# Sheet1.net
KiCad netlist of a schematic drawn in Altium Designer
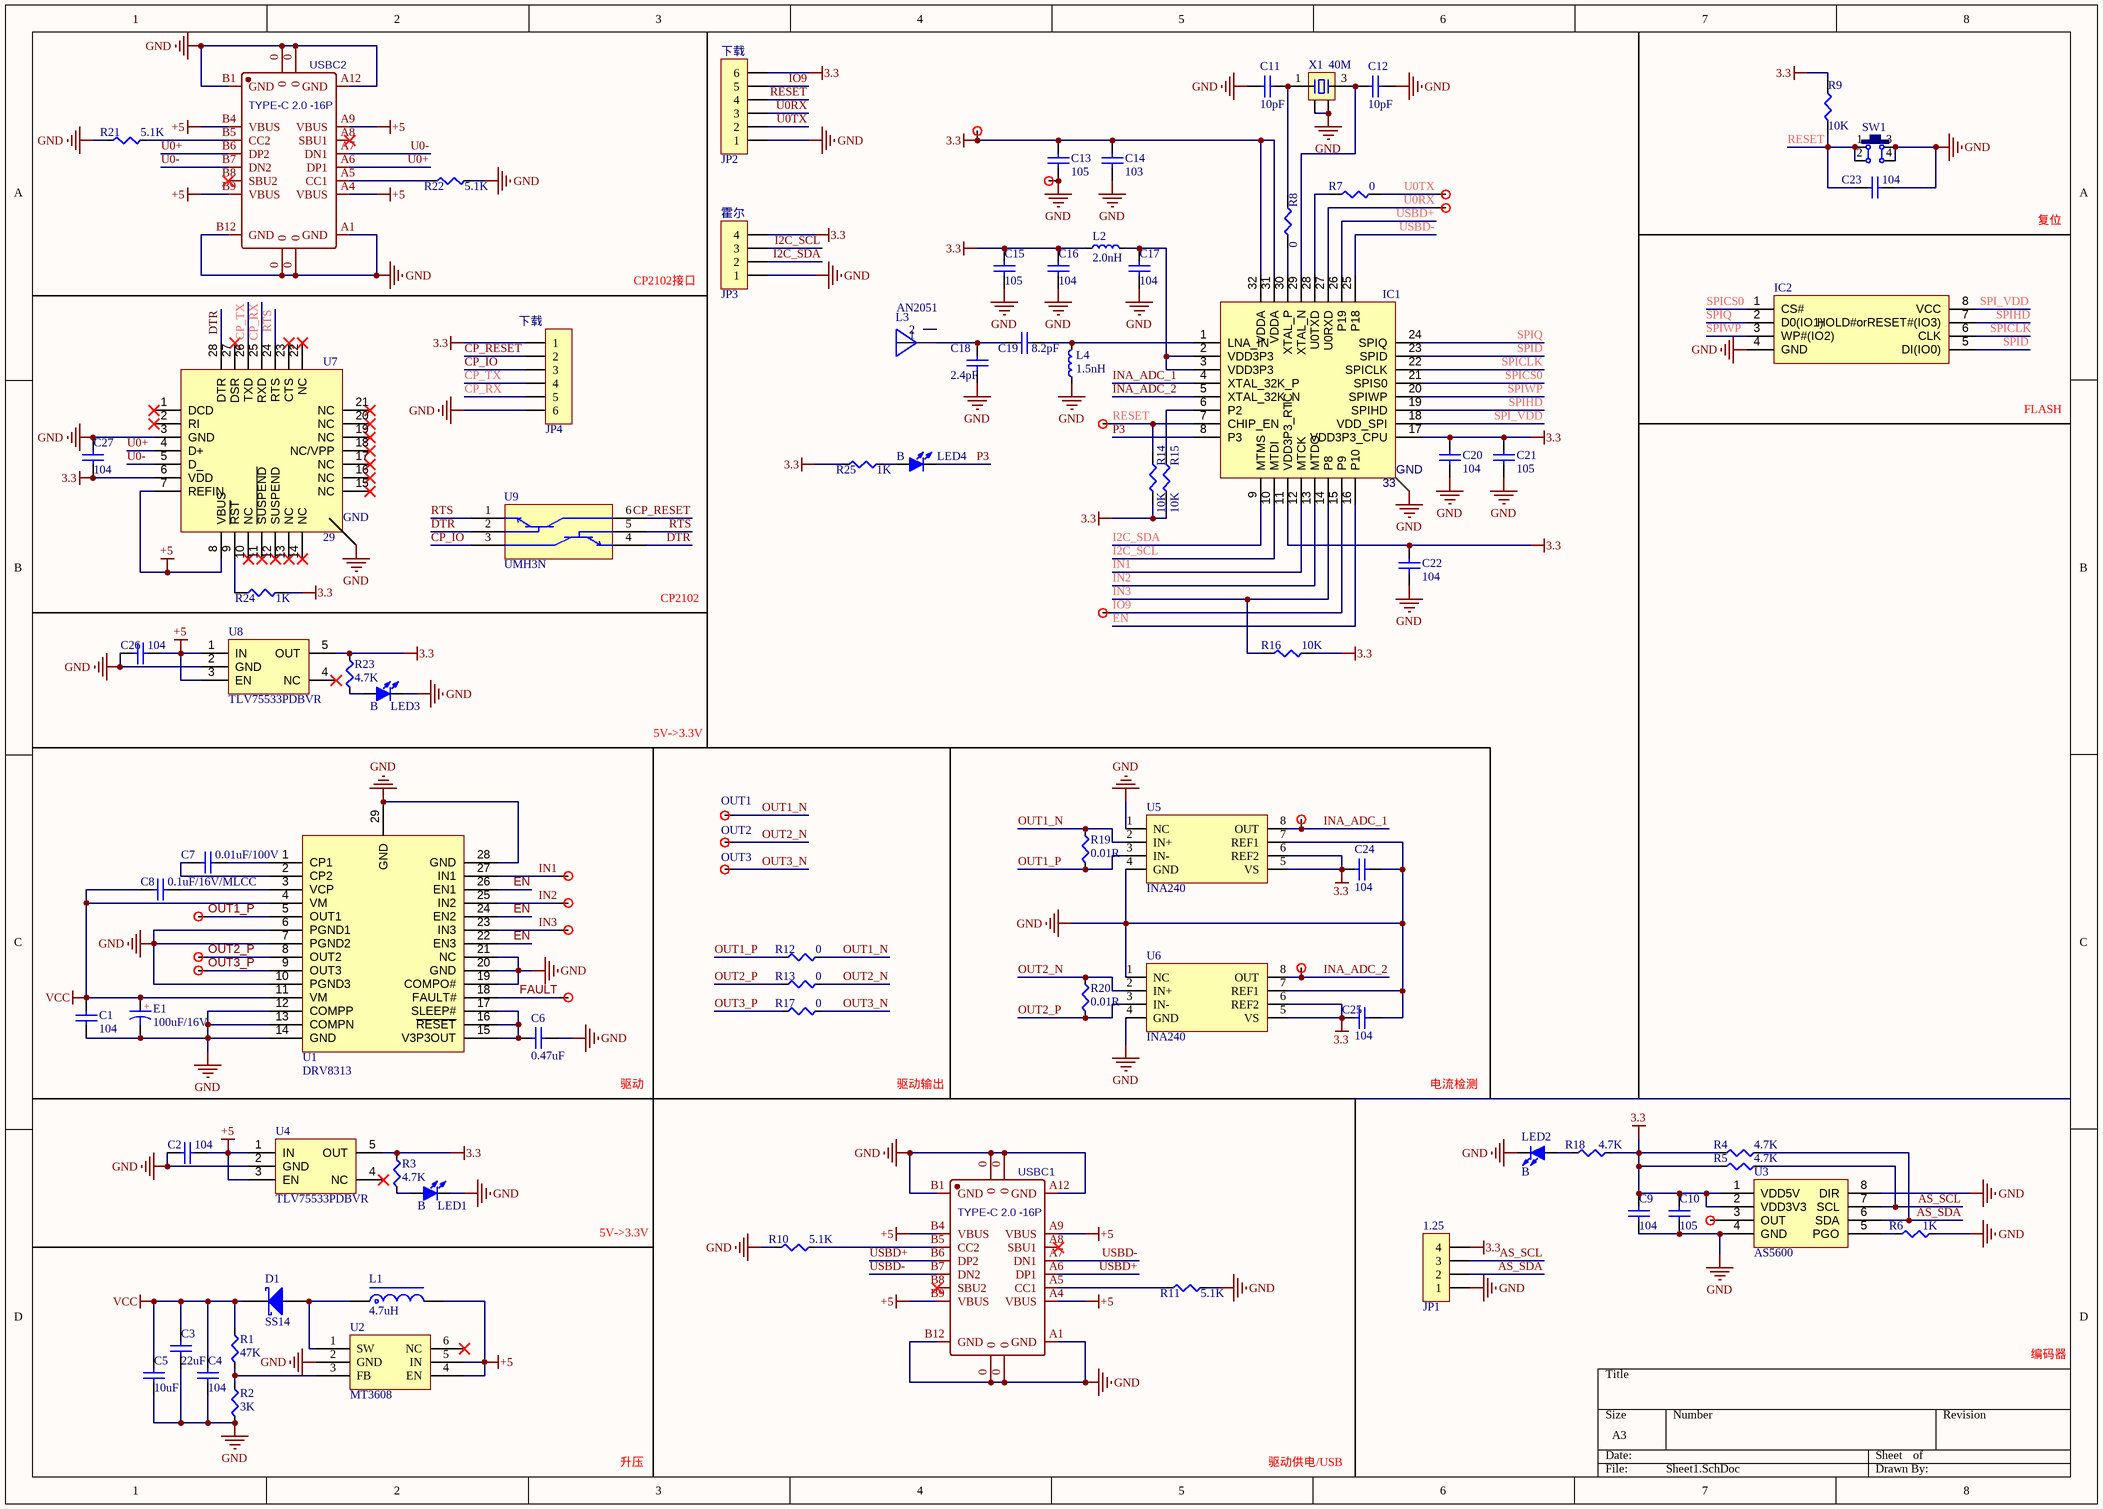
[diagram p0: Sheet1.SchDoc]

(export (version "E")
  (design (tool "Eeschema 10.0.6"))
  (components
    (comp (ref "C1")
      (value "104")
      (footprint "C 0603_L")
      (description "贴片电容")
      (libsource (lib "0.1 - 电阻-电容-电感") (part "C"))
    )
    (comp (ref "C2")
      (value "104")
      (footprint "C 0603_L")
      (description "贴片电容")
      (libsource (lib "0.1 - 电阻-电容-电感") (part "C"))
    )
    (comp (ref "C3")
      (value "22uF")
      (footprint "C 1206_L")
      (description "贴片电容")
      (libsource (lib "0.1 - 电阻-电容-电感") (part "C"))
    )
    (comp (ref "C4")
      (value "104")
      (footprint "C 0603_L")
      (description "贴片电容")
      (libsource (lib "0.1 - 电阻-电容-电感") (part "C"))
    )
    (comp (ref "C5")
      (value "10uF")
      (footprint "C 0603_L")
      (description "贴片电容")
      (libsource (lib "0.1 - 电阻-电容-电感") (part "C"))
    )
    (comp (ref "C6")
      (value "0.47uF")
      (footprint "C 0603_L")
      (description "贴片电容")
      (libsource (lib "0.1 - 电阻-电容-电感") (part "C"))
    )
    (comp (ref "C7")
      (value "0.01uF/100V")
      (footprint "C 0603_L")
      (description "贴片电容")
      (libsource (lib "0.1 - 电阻-电容-电感") (part "C"))
    )
    (comp (ref "C8")
      (value "0.1uF/16V/MLCC")
      (footprint "C 0603_L")
      (description "贴片电容")
      (libsource (lib "0.1 - 电阻-电容-电感") (part "C"))
    )
    (comp (ref "C9")
      (value "104")
      (footprint "C 0603_L")
      (description "贴片电容")
      (libsource (lib "0.1 - 电阻-电容-电感") (part "C"))
    )
    (comp (ref "C10")
      (value "105")
      (footprint "C 0603_L")
      (description "贴片电容")
      (libsource (lib "0.1 - 电阻-电容-电感") (part "C"))
    )
    (comp (ref "C11")
      (value "10pF")
      (footprint "C 0603_L")
      (description "贴片电容")
      (libsource (lib "0.1 - 电阻-电容-电感") (part "C"))
    )
    (comp (ref "C12")
      (value "10pF")
      (footprint "C 0603_L")
      (description "贴片电容")
      (libsource (lib "0.1 - 电阻-电容-电感") (part "C"))
    )
    (comp (ref "C13")
      (value "105")
      (footprint "C 0603_L")
      (description "贴片电容")
      (libsource (lib "0.1 - 电阻-电容-电感") (part "C"))
    )
    (comp (ref "C14")
      (value "103")
      (footprint "C 0603_L")
      (description "贴片电容")
      (libsource (lib "0.1 - 电阻-电容-电感") (part "C"))
    )
    (comp (ref "C15")
      (value "105")
      (footprint "C 0603_L")
      (description "贴片电容")
      (libsource (lib "0.1 - 电阻-电容-电感") (part "C"))
    )
    (comp (ref "C16")
      (value "104")
      (footprint "C 0603_L")
      (description "贴片电容")
      (libsource (lib "0.1 - 电阻-电容-电感") (part "C"))
    )
    (comp (ref "C17")
      (value "104")
      (footprint "C 0603_L")
      (description "贴片电容")
      (libsource (lib "0.1 - 电阻-电容-电感") (part "C"))
    )
    (comp (ref "C18")
      (value "2.4pF")
      (footprint "C 0603_L")
      (description "贴片电容")
      (libsource (lib "0.1 - 电阻-电容-电感") (part "C"))
    )
    (comp (ref "C19")
      (value "8.2pF")
      (footprint "C 0603_L")
      (description "贴片电容")
      (libsource (lib "0.1 - 电阻-电容-电感") (part "C"))
    )
    (comp (ref "C20")
      (value "104")
      (footprint "C 0603_L")
      (description "贴片电容")
      (libsource (lib "0.1 - 电阻-电容-电感") (part "C"))
    )
    (comp (ref "C21")
      (value "105")
      (footprint "C 0603_L")
      (description "贴片电容")
      (libsource (lib "0.1 - 电阻-电容-电感") (part "C"))
    )
    (comp (ref "C22")
      (value "104")
      (footprint "C 0603_L")
      (description "贴片电容")
      (libsource (lib "0.1 - 电阻-电容-电感") (part "C"))
    )
    (comp (ref "C23")
      (value "104")
      (footprint "C 0603_L")
      (description "贴片电容")
      (libsource (lib "0.1 - 电阻-电容-电感") (part "C"))
    )
    (comp (ref "C24")
      (value "104")
      (footprint "C 0603_L")
      (description "贴片电容")
      (libsource (lib "0.1 - 电阻-电容-电感") (part "C"))
    )
    (comp (ref "C25")
      (value "104")
      (footprint "C 0603_L")
      (description "贴片电容")
      (libsource (lib "0.1 - 电阻-电容-电感") (part "C"))
    )
    (comp (ref "C26")
      (value "104")
      (footprint "C 0603_L")
      (description "贴片电容")
      (libsource (lib "0.1 - 电阻-电容-电感") (part "C"))
    )
    (comp (ref "C27")
      (value "104")
      (footprint "C 0603_L")
      (description "贴片电容")
      (libsource (lib "0.1 - 电阻-电容-电感") (part "C"))
    )
    (comp (ref "D1")
      (value "SS14")
      (footprint "SMA")
      (description "肖特基二极管")
      (libsource (lib "0.2 - 二极管-整流桥") (part "SS14"))
    )
    (comp (ref "E1")
      (value "100uF/16V")
      (footprint "CM D(6.3*5.4)")
      (description "贴片电解电容")
      (libsource (lib "0.1 - 电阻-电容-电感") (part "CE_SMD"))
    )
    (comp (ref "HP1")
      (value "HP")
      (footprint "HP1x0.5")
      (description "引脚测试点")
      (libsource (lib "6.6 - 焊盘") (part "HP"))
    )
    (comp (ref "HP2")
      (value "HP")
      (footprint "HP1x0.5")
      (description "引脚测试点")
      (libsource (lib "6.6 - 焊盘") (part "HP"))
    )
    (comp (ref "HP3")
      (value "HP")
      (footprint "HP1x0.5")
      (description "引脚测试点")
      (libsource (lib "6.6 - 焊盘") (part "HP"))
    )
    (comp (ref "HP4")
      (value "HP")
      (footprint "HP1x0.5")
      (description "引脚测试点")
      (libsource (lib "6.6 - 焊盘") (part "HP"))
    )
    (comp (ref "HP5")
      (value "HP")
      (footprint "HP1x0.5")
      (description "引脚测试点")
      (libsource (lib "6.6 - 焊盘") (part "HP"))
    )
    (comp (ref "HP6")
      (value "HP")
      (footprint "HP1x0.5")
      (description "引脚测试点")
      (libsource (lib "6.6 - 焊盘") (part "HP"))
    )
    (comp (ref "HP7")
      (value "HP")
      (footprint "HP1x0.5")
      (description "引脚测试点")
      (libsource (lib "6.6 - 焊盘") (part "HP"))
    )
    (comp (ref "HP8")
      (value "HP")
      (footprint "HP1x0.5")
      (description "引脚测试点")
      (libsource (lib "6.6 - 焊盘") (part "HP"))
    )
    (comp (ref "HP9")
      (value "OUT1")
      (footprint "HP1x0.5")
      (description "引脚测试点")
      (libsource (lib "6.6 - 焊盘") (part "HP"))
    )
    (comp (ref "HP10")
      (value "OUT2")
      (footprint "HP1x0.5")
      (description "引脚测试点")
      (libsource (lib "6.6 - 焊盘") (part "HP"))
    )
    (comp (ref "HP11")
      (value "OUT3")
      (footprint "HP1x0.5")
      (description "引脚测试点")
      (libsource (lib "6.6 - 焊盘") (part "HP"))
    )
    (comp (ref "HP12")
      (value "HP")
      (footprint "HP1x0.5")
      (description "引脚测试点")
      (libsource (lib "6.6 - 焊盘") (part "HP"))
    )
    (comp (ref "HP13")
      (value "HP")
      (footprint "HP1x0.5")
      (description "引脚测试点")
      (libsource (lib "6.6 - 焊盘") (part "HP"))
    )
    (comp (ref "HP14")
      (value "HP")
      (footprint "HP1x0.5")
      (description "引脚测试点")
      (libsource (lib "6.6 - 焊盘") (part "HP"))
    )
    (comp (ref "HP15")
      (value "HP")
      (footprint "HP1x0.5")
      (description "引脚测试点")
      (libsource (lib "6.6 - 焊盘") (part "HP"))
    )
    (comp (ref "HP16")
      (value "HP")
      (footprint "HP1x0.5")
      (description "引脚测试点")
      (libsource (lib "6.6 - 焊盘") (part "HP"))
    )
    (comp (ref "HP17")
      (value "HP")
      (footprint "HP1x0.5")
      (description "引脚测试点")
      (libsource (lib "6.6 - 焊盘") (part "HP"))
    )
    (comp (ref "HP18")
      (value "HP")
      (footprint "HP1x0.5")
      (description "引脚测试点")
      (libsource (lib "6.6 - 焊盘") (part "HP"))
    )
    (comp (ref "HP19")
      (value "HP")
      (footprint "HP1x0.5")
      (description "引脚测试点")
      (libsource (lib "6.6 - 焊盘") (part "HP"))
    )
    (comp (ref "IC1")
      (value "ESP32-C3")
      (footprint "ESP32-C3")
      (description "ESP32-C3 QFN-32(5x5)")
      (libsource (lib "ESP32") (part "ESP32-C3"))
    )
    (comp (ref "IC2")
      (value "W25Q64")
      (footprint "SOIC-8W")
      (libsource (lib "1.2 - 存储器-传感元件") (part "W25Q64"))
    )
    (comp (ref "JP1")
      (value "HDR-1X4")
      (footprint "MX 1.25-WI-4P")
      (description "4P接插件")
      (libsource (lib "5.0 - 接插件-脚距1.25") (part "Header 4"))
    )
    (comp (ref "JP2")
      (value "HDR-1X6")
      (footprint "MX 1.25-WI-6P")
      (description "6P接插件")
      (libsource (lib "5.0 - 接插件-脚距1.25") (part "Header 6"))
    )
    (comp (ref "JP3")
      (value "HDR-1X4")
      (footprint "MX 1.25-WI-4P")
      (description "4P接插件")
      (libsource (lib "5.0 - 接插件-脚距1.25") (part "Header 4"))
    )
    (comp (ref "JP4")
      (value "HDR-1X6")
      (footprint "MX 1.25-WI-6P")
      (description "6P接插件")
      (libsource (lib "") (part "Header 6_1"))
    )
    (comp (ref "L1")
      (value "4.7uH")
      (footprint "NR4020")
      (description "NR磁胶电感")
      (libsource (lib "0.1 - 电阻-电容-电感") (part "L-NR"))
    )
    (comp (ref "L2")
      (value "2.0nH")
      (footprint "L 0805")
      (description "小功率贴片电感")
      (libsource (lib "0.1 - 电阻-电容-电感") (part "L"))
    )
    (comp (ref "L3")
      (value "AN2051")
      (footprint "AN2051-245 2.4G")
      (description "AN2051-245 2.4G蓝牙wifi 贴片 2051")
      (libsource (lib "1.8 - WiFi天线-SMA射频座") (part "AN2051"))
    )
    (comp (ref "L4")
      (value "1.5nH")
      (footprint "L 0805")
      (description "小功率贴片电感")
      (libsource (lib "0.1 - 电阻-电容-电感") (part "L"))
    )
    (comp (ref "LED1")
      (value "B")
      (footprint "LED 0603B")
      (description "贴片LED")
      (libsource (lib "0.3 - LED发光二极管") (part "B"))
    )
    (comp (ref "LED2")
      (value "B")
      (footprint "LED 0603B")
      (description "贴片LED")
      (libsource (lib "0.3 - LED发光二极管") (part "B"))
    )
    (comp (ref "LED3")
      (value "B")
      (footprint "LED 0603B")
      (description "贴片LED")
      (libsource (lib "0.3 - LED发光二极管") (part "B"))
    )
    (comp (ref "LED4")
      (value "B")
      (footprint "LED 0603B")
      (description "贴片LED")
      (libsource (lib "0.3 - LED发光二极管") (part "B"))
    )
    (comp (ref "R1")
      (value "47K")
      (footprint "R 0603_L")
      (description "贴片电阻")
      (libsource (lib "0.1 - 电阻-电容-电感") (part "R"))
    )
    (comp (ref "R2")
      (value "3K")
      (footprint "R 0603_L")
      (description "贴片电阻")
      (libsource (lib "0.1 - 电阻-电容-电感") (part "R"))
    )
    (comp (ref "R3")
      (value "4.7K")
      (footprint "R 0603_L")
      (description "贴片电阻")
      (libsource (lib "0.1 - 电阻-电容-电感") (part "R"))
    )
    (comp (ref "R4")
      (value "4.7K")
      (footprint "R 0603_L")
      (description "贴片电阻")
      (libsource (lib "0.1 - 电阻-电容-电感") (part "R"))
    )
    (comp (ref "R5")
      (value "4.7K")
      (footprint "R 0603_L")
      (description "贴片电阻")
      (libsource (lib "0.1 - 电阻-电容-电感") (part "R"))
    )
    (comp (ref "R6")
      (value "1K")
      (footprint "R 0603_L")
      (description "贴片电阻")
      (libsource (lib "0.1 - 电阻-电容-电感") (part "R"))
    )
    (comp (ref "R7")
      (value "0")
      (footprint "R 0603_L")
      (description "贴片电阻")
      (libsource (lib "") (part "R_1"))
    )
    (comp (ref "R8")
      (value "0")
      (footprint "R 0603_L")
      (description "贴片电阻")
      (libsource (lib "") (part "R_1"))
    )
    (comp (ref "R9")
      (value "10K")
      (footprint "R 0603_L")
      (description "贴片电阻")
      (libsource (lib "") (part "R_1"))
    )
    (comp (ref "R10")
      (value "5.1K")
      (footprint "R 0603_L")
      (description "贴片电阻")
      (libsource (lib "0.1 - 电阻-电容-电感") (part "R"))
    )
    (comp (ref "R11")
      (value "5.1K")
      (footprint "R 0603_L")
      (description "贴片电阻")
      (libsource (lib "0.1 - 电阻-电容-电感") (part "R"))
    )
    (comp (ref "R12")
      (value "0")
      (footprint "R 0603_L")
      (description "贴片电阻")
      (libsource (lib "0.1 - 电阻-电容-电感") (part "R"))
    )
    (comp (ref "R13")
      (value "0")
      (footprint "R 0603_L")
      (description "贴片电阻")
      (libsource (lib "0.1 - 电阻-电容-电感") (part "R"))
    )
    (comp (ref "R14")
      (value "10K")
      (footprint "R 0603_L")
      (description "贴片电阻")
      (libsource (lib "") (part "R_1"))
    )
    (comp (ref "R15")
      (value "10K")
      (footprint "R 0603_L")
      (description "贴片电阻")
      (libsource (lib "") (part "R_1"))
    )
    (comp (ref "R16")
      (value "10K")
      (footprint "R 0603_L")
      (description "贴片电阻")
      (libsource (lib "") (part "R_1"))
    )
    (comp (ref "R17")
      (value "0")
      (footprint "R 0603_L")
      (description "贴片电阻")
      (libsource (lib "0.1 - 电阻-电容-电感") (part "R"))
    )
    (comp (ref "R18")
      (value "4.7K")
      (footprint "R 0603_L")
      (description "贴片电阻")
      (libsource (lib "0.1 - 电阻-电容-电感") (part "R"))
    )
    (comp (ref "R19")
      (value "0.01R")
      (footprint "R 1206_L")
      (description "贴片电阻")
      (libsource (lib "0.1 - 电阻-电容-电感") (part "R"))
    )
    (comp (ref "R20")
      (value "0.01R")
      (footprint "R 1210_L")
      (description "贴片电阻")
      (libsource (lib "0.1 - 电阻-电容-电感") (part "R"))
    )
    (comp (ref "R21")
      (value "5.1K")
      (footprint "R 0603_L")
      (description "贴片电阻")
      (libsource (lib "0.1 - 电阻-电容-电感") (part "R"))
    )
    (comp (ref "R22")
      (value "5.1K")
      (footprint "R 0603_L")
      (description "贴片电阻")
      (libsource (lib "0.1 - 电阻-电容-电感") (part "R"))
    )
    (comp (ref "R23")
      (value "4.7K")
      (footprint "R 0603_L")
      (description "贴片电阻")
      (libsource (lib "0.1 - 电阻-电容-电感") (part "R"))
    )
    (comp (ref "R24")
      (value "1K")
      (footprint "R 0603_L")
      (description "贴片电阻")
      (libsource (lib "") (part "R_1"))
    )
    (comp (ref "R25")
      (value "1K")
      (footprint "R 0603_L")
      (description "贴片电阻")
      (libsource (lib "0.1 - 电阻-电容-电感") (part "R"))
    )
    (comp (ref "SW1")
      (value "3.2x4.2x5")
      (footprint "TSW SMD 3.2*4.2*2.5")
      (description "贴片4.2*3.2轻触开关")
      (libsource (lib "0.7 - 常用按键-开关-蜂鸣器-电池") (part "TSW SMD-3.2x4.2"))
    )
    (comp (ref "U1")
      (value "DRV8313")
      (footprint "HTSSOP-28-EP-4.5mm")
      (description "DRV8313 无刷直流BLDC 8V~60V三路半H桥驱动器IC")
      (libsource (lib "1.0 - 常见芯片") (part "DRV8313"))
    )
    (comp (ref "U2")
      (value "MT3608")
      (footprint "SOT23-6L")
      (description "DCDC 升压1.2MHZ 2A\r\n97%")
      (libsource (lib "1.1 - 电源类芯片") (part "MT3608"))
    )
    (comp (ref "U3")
      (value "AS5600")
      (footprint "SOIC-8")
      (description "AS5600 12bit磁角度位置传感器")
      (libsource (lib "1.0 - 常见芯片") (part "AS5600"))
    )
    (comp (ref "U4")
      (value "TLV75533PDBVR")
      (footprint "SOT23-5L")
      (description "Vout:3.3V;Vin:1.45~5.5V,500ma;低压降")
      (libsource (lib "1.1 - 电源类芯片") (part "TLV75533PDBVR"))
    )
    (comp (ref "U5")
      (value "INA240")
      (footprint "TSSOP8_N")
      (description "具有增强的 PWM 抑制能力的 -4V 至 80V、双向、超精密电流感应放大器")
      (libsource (lib "1.1 - 电源类芯片") (part "INA240"))
    )
    (comp (ref "U6")
      (value "INA240")
      (footprint "TSSOP8_N")
      (description "具有增强的 PWM 抑制能力的 -4V 至 80V、双向、超精密电流感应放大器")
      (libsource (lib "1.1 - 电源类芯片") (part "INA240"))
    )
    (comp (ref "U7")
      (value "CP2102")
      (footprint "QFN28 5x5_M")
      (description "USB转TTL")
      (libsource (lib "1.0 - 常见芯片") (part "CP2102"))
    )
    (comp (ref "U8")
      (value "TLV75533PDBVR")
      (footprint "SOT23-5L")
      (description "Vout:3.3V;Vin:1.45~5.5V,500ma;低压降")
      (libsource (lib "1.1 - 电源类芯片") (part "TLV75533PDBVR"))
    )
    (comp (ref "U9")
      (value "UMH3N")
      (footprint "SOT-363")
      (description "2NPN预偏式(双)")
      (libsource (lib "0.4 - 三极管-场效应管-可控硅") (part "UMH3N"))
    )
    (comp (ref "USBC1")
      (value "TYPE-C 2.0 -16P")
      (footprint "USB-C-SMD_TYPE-C-USB-5")
      (description "USB2.0 Type-C 母座 16Pin")
      (libsource (lib "0.8 - 以太网-音频-USB插座") (part "USB2.0 Type-C 16Pin母座"))
    )
    (comp (ref "USBC2")
      (value "TYPE-C 2.0 -16P")
      (footprint "USB-C-SMD_TYPE-C-USB-5")
      (description "USB2.0 Type-C 母座 16Pin")
      (libsource (lib "0.8 - 以太网-音频-USB插座") (part "USB2.0 Type-C 16Pin母座"))
    )
    (comp (ref "X1")
      (value "40M")
      (footprint "OSC 3225-4P")
      (description "4脚无源晶振")
      (libsource (lib "0.5 - 保险丝-晶振-光耦") (part "XTAL-4P"))
    )
  )
  (nets
    (net (code "1") (name "+5") (class "Default")
      (node (ref "C2") (pin "2") (pinfunction "2_2") (pintype "passive"))
      (node (ref "C26") (pin "2") (pinfunction "2_2") (pintype "passive"))
      (node (ref "L1") (pin "2") (pinfunction "2_2") (pintype "passive"))
      (node (ref "U2") (pin "4") (pinfunction "EN_4") (pintype "passive"))
      (node (ref "U2") (pin "5") (pinfunction "IN_5") (pintype "passive"))
      (node (ref "U4") (pin "1") (pinfunction "IN_1") (pintype "passive"))
      (node (ref "U4") (pin "3") (pinfunction "EN_3") (pintype "passive"))
      (node (ref "U7") (pin "7") (pinfunction "REFIN_7") (pintype "passive"))
      (node (ref "U7") (pin "8") (pinfunction "VBUS_8") (pintype "passive"))
      (node (ref "U8") (pin "1") (pinfunction "IN_1") (pintype "passive"))
      (node (ref "U8") (pin "3") (pinfunction "EN_3") (pintype "passive"))
      (node (ref "USBC1") (pin "A4") (pinfunction "VBUS_A4") (pintype "passive"))
      (node (ref "USBC1") (pin "A9") (pinfunction "VBUS_A9") (pintype "passive"))
      (node (ref "USBC1") (pin "B4") (pinfunction "VBUS_B4") (pintype "passive"))
      (node (ref "USBC1") (pin "B9") (pinfunction "VBUS_B9") (pintype "passive"))
      (node (ref "USBC2") (pin "A4") (pinfunction "VBUS_A4") (pintype "passive"))
      (node (ref "USBC2") (pin "A9") (pinfunction "VBUS_A9") (pintype "passive"))
      (node (ref "USBC2") (pin "B4") (pinfunction "VBUS_B4") (pintype "passive"))
      (node (ref "USBC2") (pin "B9") (pinfunction "VBUS_B9") (pintype "passive"))
    )
    (net (code "2") (name "/AS_SCL") (class "Default")
      (node (ref "JP1") (pin "3") (pinfunction "3_3") (pintype "passive"))
      (node (ref "R5") (pin "2") (pinfunction "2_2") (pintype "passive"))
      (node (ref "U3") (pin "7") (pinfunction "SCL_7") (pintype "passive"))
    )
    (net (code "3") (name "/AS_SDA") (class "Default")
      (node (ref "JP1") (pin "2") (pinfunction "2_2") (pintype "passive"))
      (node (ref "R4") (pin "2") (pinfunction "2_2") (pintype "passive"))
      (node (ref "U3") (pin "6") (pinfunction "SDA_6") (pintype "passive"))
    )
    (net (code "4") (name "/CP_IO") (class "Default")
      (node (ref "JP4") (pin "3") (pinfunction "3_3") (pintype "passive"))
      (node (ref "U9") (pin "3") (pinfunction "C2_3") (pintype "passive"))
    )
    (net (code "5") (name "/CP_RESET") (class "Default")
      (node (ref "JP4") (pin "2") (pinfunction "2_2") (pintype "passive"))
      (node (ref "U9") (pin "6") (pinfunction "C1_6") (pintype "passive"))
    )
    (net (code "6") (name "/CP_RX") (class "Default")
      (node (ref "JP4") (pin "5") (pinfunction "5_5") (pintype "passive"))
      (node (ref "U7") (pin "25") (pinfunction "RXD_25") (pintype "passive"))
    )
    (net (code "7") (name "/CP_TX") (class "Default")
      (node (ref "JP4") (pin "4") (pinfunction "4_4") (pintype "passive"))
      (node (ref "U7") (pin "26") (pinfunction "TXD_26") (pintype "passive"))
    )
    (net (code "8") (name "/DTR") (class "Default")
      (node (ref "U7") (pin "28") (pinfunction "DTR_28") (pintype "passive"))
      (node (ref "U9") (pin "2") (pinfunction "B2_2") (pintype "passive"))
      (node (ref "U9") (pin "4") (pinfunction "E2_4") (pintype "passive"))
    )
    (net (code "9") (name "/EN") (class "Default")
      (node (ref "IC1") (pin "16") (pinfunction "P10_16") (pintype "power_in"))
      (node (ref "U1") (pin "22") (pinfunction "EN3_22") (pintype "passive"))
      (node (ref "U1") (pin "24") (pinfunction "EN2_24") (pintype "passive"))
      (node (ref "U1") (pin "26") (pinfunction "EN1_26") (pintype "passive"))
    )
    (net (code "10") (name "/FAULT") (class "Default")
      (node (ref "HP7") (pin "1") (pinfunction "1_1") (pintype "passive"))
      (node (ref "U1") (pin "18") (pinfunction "FAULT#_18") (pintype "passive"))
    )
    (net (code "11") (name "/I2C_SCL") (class "Default")
      (node (ref "IC1") (pin "10") (pinfunction "MTDI_10") (pintype "power_in"))
      (node (ref "JP3") (pin "3") (pinfunction "3_3") (pintype "passive"))
    )
    (net (code "12") (name "/I2C_SDA") (class "Default")
      (node (ref "IC1") (pin "9") (pinfunction "MTMS_9") (pintype "power_in"))
      (node (ref "JP3") (pin "2") (pinfunction "2_2") (pintype "passive"))
    )
    (net (code "13") (name "/IN1") (class "Default")
      (node (ref "HP1") (pin "1") (pinfunction "1_1") (pintype "passive"))
      (node (ref "IC1") (pin "12") (pinfunction "MTCK_12") (pintype "power_in"))
      (node (ref "U1") (pin "27") (pinfunction "IN1_27") (pintype "passive"))
    )
    (net (code "14") (name "/IN2") (class "Default")
      (node (ref "HP2") (pin "1") (pinfunction "1_1") (pintype "passive"))
      (node (ref "IC1") (pin "13") (pinfunction "MTDO_13") (pintype "power_in"))
      (node (ref "U1") (pin "25") (pinfunction "IN2_25") (pintype "passive"))
    )
    (net (code "15") (name "/IN3") (class "Default")
      (node (ref "HP4") (pin "1") (pinfunction "1_1") (pintype "passive"))
      (node (ref "IC1") (pin "14") (pinfunction "P8_14") (pintype "power_in"))
      (node (ref "R16") (pin "1") (pinfunction "1_1") (pintype "passive"))
      (node (ref "U1") (pin "23") (pinfunction "IN3_23") (pintype "passive"))
    )
    (net (code "16") (name "/INA_ADC_1") (class "Default")
      (node (ref "HP12") (pin "1") (pinfunction "1_1") (pintype "passive"))
      (node (ref "IC1") (pin "4") (pinfunction "XTAL_32K_P_4") (pintype "power_in"))
      (node (ref "U5") (pin "8") (pinfunction "OUT_8") (pintype "passive"))
    )
    (net (code "17") (name "/INA_ADC_2") (class "Default")
      (node (ref "HP14") (pin "1") (pinfunction "1_1") (pintype "passive"))
      (node (ref "IC1") (pin "5") (pinfunction "XTAL_32K_N_5") (pintype "power_in"))
      (node (ref "U6") (pin "8") (pinfunction "OUT_8") (pintype "passive"))
    )
    (net (code "18") (name "/IO9") (class "Default")
      (node (ref "HP17") (pin "1") (pinfunction "1_1") (pintype "passive"))
      (node (ref "IC1") (pin "15") (pinfunction "P9_15") (pintype "power_in"))
      (node (ref "JP2") (pin "5") (pinfunction "5_5") (pintype "passive"))
    )
    (net (code "19") (name "/OUT1_N") (class "Default")
      (node (ref "HP9") (pin "1") (pinfunction "1_1") (pintype "passive"))
      (node (ref "R12") (pin "2") (pinfunction "2_2") (pintype "passive"))
      (node (ref "R19") (pin "2") (pinfunction "2_2") (pintype "passive"))
      (node (ref "U5") (pin "2") (pinfunction "IN+_2") (pintype "passive"))
    )
    (net (code "20") (name "/OUT1_P") (class "Default")
      (node (ref "HP3") (pin "1") (pinfunction "1_1") (pintype "passive"))
      (node (ref "R12") (pin "1") (pinfunction "1_1") (pintype "passive"))
      (node (ref "R19") (pin "1") (pinfunction "1_1") (pintype "passive"))
      (node (ref "U1") (pin "5") (pinfunction "OUT1_5") (pintype "passive"))
      (node (ref "U5") (pin "3") (pinfunction "IN-_3") (pintype "passive"))
    )
    (net (code "21") (name "/OUT2_N") (class "Default")
      (node (ref "HP10") (pin "1") (pinfunction "1_1") (pintype "passive"))
      (node (ref "R13") (pin "2") (pinfunction "2_2") (pintype "passive"))
      (node (ref "R20") (pin "2") (pinfunction "2_2") (pintype "passive"))
      (node (ref "U6") (pin "2") (pinfunction "IN+_2") (pintype "passive"))
    )
    (net (code "22") (name "/OUT2_P") (class "Default")
      (node (ref "HP5") (pin "1") (pinfunction "1_1") (pintype "passive"))
      (node (ref "R13") (pin "1") (pinfunction "1_1") (pintype "passive"))
      (node (ref "R20") (pin "1") (pinfunction "1_1") (pintype "passive"))
      (node (ref "U1") (pin "8") (pinfunction "OUT2_8") (pintype "passive"))
      (node (ref "U6") (pin "3") (pinfunction "IN-_3") (pintype "passive"))
    )
    (net (code "23") (name "/OUT3_N") (class "Default")
      (node (ref "HP11") (pin "1") (pinfunction "1_1") (pintype "passive"))
      (node (ref "R17") (pin "2") (pinfunction "2_2") (pintype "passive"))
    )
    (net (code "24") (name "/OUT3_P") (class "Default")
      (node (ref "HP6") (pin "1") (pinfunction "1_1") (pintype "passive"))
      (node (ref "R17") (pin "1") (pinfunction "1_1") (pintype "passive"))
      (node (ref "U1") (pin "9") (pinfunction "OUT3_9") (pintype "passive"))
    )
    (net (code "25") (name "/P3") (class "Default")
      (node (ref "IC1") (pin "8") (pinfunction "P3_8") (pintype "power_in"))
      (node (ref "LED4") (pin "2") (pinfunction "K_2") (pintype "passive"))
    )
    (net (code "26") (name "/RESET") (class "Default")
      (node (ref "C23") (pin "1") (pinfunction "1_1") (pintype "passive"))
      (node (ref "HP16") (pin "1") (pinfunction "1_1") (pintype "passive"))
      (node (ref "IC1") (pin "7") (pinfunction "CHIP_EN_7") (pintype "power_in"))
      (node (ref "JP2") (pin "4") (pinfunction "4_4") (pintype "passive"))
      (node (ref "R14") (pin "2") (pinfunction "2_2") (pintype "passive"))
      (node (ref "R9") (pin "1") (pinfunction "1_1") (pintype "passive"))
      (node (ref "SW1") (pin "1") (pinfunction "1_1") (pintype "passive"))
      (node (ref "SW1") (pin "2") (pinfunction "2_2") (pintype "passive"))
    )
    (net (code "27") (name "/RTS") (class "Default")
      (node (ref "U7") (pin "24") (pinfunction "RTS_24") (pintype "passive"))
      (node (ref "U9") (pin "1") (pinfunction "E1_1") (pintype "passive"))
      (node (ref "U9") (pin "5") (pinfunction "B2_5") (pintype "passive"))
    )
    (net (code "28") (name "/SPICLK") (class "Default")
      (node (ref "IC1") (pin "22") (pinfunction "SPICLK_22") (pintype "power_in"))
      (node (ref "IC2") (pin "6") (pinfunction "CLK_6") (pintype "power_in"))
    )
    (net (code "29") (name "/SPICS0") (class "Default")
      (node (ref "IC1") (pin "21") (pinfunction "SPIS0_21") (pintype "power_in"))
      (node (ref "IC2") (pin "1") (pinfunction "CS#_1") (pintype "power_in"))
    )
    (net (code "30") (name "/SPID") (class "Default")
      (node (ref "IC1") (pin "23") (pinfunction "SPID_23") (pintype "power_in"))
      (node (ref "IC2") (pin "5") (pinfunction "DI(IO0)_5") (pintype "power_in"))
    )
    (net (code "31") (name "/SPIHD") (class "Default")
      (node (ref "IC1") (pin "19") (pinfunction "SPIHD_19") (pintype "power_in"))
      (node (ref "IC2") (pin "7") (pinfunction "HOLD#orRESET#(IO3)_7") (pintype "power_in"))
    )
    (net (code "32") (name "/SPIQ") (class "Default")
      (node (ref "IC1") (pin "24") (pinfunction "SPIQ_24") (pintype "power_in"))
      (node (ref "IC2") (pin "2") (pinfunction "D0(IO1)_2") (pintype "power_in"))
    )
    (net (code "33") (name "/SPIWP") (class "Default")
      (node (ref "IC1") (pin "20") (pinfunction "SPIWP_20") (pintype "power_in"))
      (node (ref "IC2") (pin "3") (pinfunction "WP#(IO2)_3") (pintype "power_in"))
    )
    (net (code "34") (name "/SPI_VDD") (class "Default")
      (node (ref "IC1") (pin "18") (pinfunction "VDD_SPI_18") (pintype "power_in"))
      (node (ref "IC2") (pin "8") (pinfunction "VCC_8") (pintype "power_in"))
    )
    (net (code "35") (name "/U0+") (class "Default")
      (node (ref "U7") (pin "4") (pinfunction "D+_4") (pintype "passive"))
      (node (ref "USBC2") (pin "A6") (pinfunction "DP1_A6") (pintype "passive"))
      (node (ref "USBC2") (pin "B6") (pinfunction "DP2_B6") (pintype "passive"))
    )
    (net (code "36") (name "/U0-") (class "Default")
      (node (ref "U7") (pin "5") (pinfunction "D__5") (pintype "passive"))
      (node (ref "USBC2") (pin "A7") (pinfunction "DN1_A7") (pintype "passive"))
      (node (ref "USBC2") (pin "B7") (pinfunction "DN2_B7") (pintype "passive"))
    )
    (net (code "37") (name "/U0RX") (class "Default")
      (node (ref "HP15") (pin "1") (pinfunction "1_1") (pintype "passive"))
      (node (ref "IC1") (pin "27") (pinfunction "U0RXD_27") (pintype "power_in"))
      (node (ref "JP2") (pin "3") (pinfunction "3_3") (pintype "passive"))
    )
    (net (code "38") (name "/U0TX") (class "Default")
      (node (ref "HP13") (pin "1") (pinfunction "1_1") (pintype "passive"))
      (node (ref "JP2") (pin "2") (pinfunction "2_2") (pintype "passive"))
      (node (ref "R7") (pin "2") (pinfunction "2_2") (pintype "passive"))
    )
    (net (code "39") (name "/USBD+") (class "Default")
      (node (ref "IC1") (pin "26") (pinfunction "P19_26") (pintype "power_in"))
      (node (ref "USBC1") (pin "A6") (pinfunction "DP1_A6") (pintype "passive"))
      (node (ref "USBC1") (pin "B6") (pinfunction "DP2_B6") (pintype "passive"))
    )
    (net (code "40") (name "/USBD-") (class "Default")
      (node (ref "IC1") (pin "25") (pinfunction "P18_25") (pintype "power_in"))
      (node (ref "USBC1") (pin "A7") (pinfunction "DN1_A7") (pintype "passive"))
      (node (ref "USBC1") (pin "B7") (pinfunction "DN2_B7") (pintype "passive"))
    )
    (net (code "41") (name "3.3") (class "Default")
      (node (ref "C10") (pin "2") (pinfunction "2_2") (pintype "passive"))
      (node (ref "C13") (pin "2") (pinfunction "2_2") (pintype "passive"))
      (node (ref "C14") (pin "2") (pinfunction "2_2") (pintype "passive"))
      (node (ref "C15") (pin "2") (pinfunction "2_2") (pintype "passive"))
      (node (ref "C16") (pin "2") (pinfunction "2_2") (pintype "passive"))
      (node (ref "C20") (pin "2") (pinfunction "2_2") (pintype "passive"))
      (node (ref "C21") (pin "2") (pinfunction "2_2") (pintype "passive"))
      (node (ref "C22") (pin "2") (pinfunction "2_2") (pintype "passive"))
      (node (ref "C24") (pin "2") (pinfunction "2_2") (pintype "passive"))
      (node (ref "C25") (pin "1") (pinfunction "1_1") (pintype "passive"))
      (node (ref "C27") (pin "1") (pinfunction "1_1") (pintype "passive"))
      (node (ref "C9") (pin "2") (pinfunction "2_2") (pintype "passive"))
      (node (ref "HP18") (pin "1") (pinfunction "1_1") (pintype "passive"))
      (node (ref "IC1") (pin "11") (pinfunction "VDD3P3_RTC_11") (pintype "power_in"))
      (node (ref "IC1") (pin "17") (pinfunction "VDD3P3_CPU_17") (pintype "power_in"))
      (node (ref "IC1") (pin "31") (pinfunction "VDDA_31") (pintype "power_in"))
      (node (ref "IC1") (pin "32") (pinfunction "VDDA_32") (pintype "power_in"))
      (node (ref "JP1") (pin "4") (pinfunction "4_4") (pintype "passive"))
      (node (ref "JP2") (pin "6") (pinfunction "6_6") (pintype "passive"))
      (node (ref "JP3") (pin "4") (pinfunction "4_4") (pintype "passive"))
      (node (ref "JP4") (pin "1") (pinfunction "1_1") (pintype "passive"))
      (node (ref "L2") (pin "1") (pinfunction "1_1") (pintype "passive"))
      (node (ref "R14") (pin "1") (pinfunction "1_1") (pintype "passive"))
      (node (ref "R15") (pin "1") (pinfunction "1_1") (pintype "passive"))
      (node (ref "R16") (pin "2") (pinfunction "2_2") (pintype "passive"))
      (node (ref "R18") (pin "2") (pinfunction "2_2") (pintype "passive"))
      (node (ref "R23") (pin "2") (pinfunction "2_2") (pintype "passive"))
      (node (ref "R24") (pin "1") (pinfunction "1_1") (pintype "passive"))
      (node (ref "R25") (pin "1") (pinfunction "1_1") (pintype "passive"))
      (node (ref "R3") (pin "2") (pinfunction "2_2") (pintype "passive"))
      (node (ref "R4") (pin "1") (pinfunction "1_1") (pintype "passive"))
      (node (ref "R5") (pin "1") (pinfunction "1_1") (pintype "passive"))
      (node (ref "R9") (pin "2") (pinfunction "2_2") (pintype "passive"))
      (node (ref "U3") (pin "1") (pinfunction "VDD5V_1") (pintype "passive"))
      (node (ref "U3") (pin "2") (pinfunction "VDD3V3_2") (pintype "passive"))
      (node (ref "U4") (pin "5") (pinfunction "OUT_5") (pintype "passive"))
      (node (ref "U5") (pin "5") (pinfunction "VS_5") (pintype "passive"))
      (node (ref "U5") (pin "6") (pinfunction "REF2_6") (pintype "passive"))
      (node (ref "U6") (pin "5") (pinfunction "VS_5") (pintype "passive"))
      (node (ref "U6") (pin "6") (pinfunction "REF2_6") (pintype "passive"))
      (node (ref "U7") (pin "6") (pinfunction "VDD_6") (pintype "passive"))
      (node (ref "U8") (pin "5") (pinfunction "OUT_5") (pintype "passive"))
    )
    (net (code "42") (name "GND") (class "Default")
      (node (ref "C1") (pin "1") (pinfunction "1_1") (pintype "passive"))
      (node (ref "C10") (pin "1") (pinfunction "1_1") (pintype "passive"))
      (node (ref "C11") (pin "1") (pinfunction "1_1") (pintype "passive"))
      (node (ref "C12") (pin "2") (pinfunction "2_2") (pintype "passive"))
      (node (ref "C13") (pin "1") (pinfunction "1_1") (pintype "passive"))
      (node (ref "C14") (pin "1") (pinfunction "1_1") (pintype "passive"))
      (node (ref "C15") (pin "1") (pinfunction "1_1") (pintype "passive"))
      (node (ref "C16") (pin "1") (pinfunction "1_1") (pintype "passive"))
      (node (ref "C17") (pin "1") (pinfunction "1_1") (pintype "passive"))
      (node (ref "C18") (pin "1") (pinfunction "1_1") (pintype "passive"))
      (node (ref "C2") (pin "1") (pinfunction "1_1") (pintype "passive"))
      (node (ref "C20") (pin "1") (pinfunction "1_1") (pintype "passive"))
      (node (ref "C21") (pin "1") (pinfunction "1_1") (pintype "passive"))
      (node (ref "C22") (pin "1") (pinfunction "1_1") (pintype "passive"))
      (node (ref "C23") (pin "2") (pinfunction "2_2") (pintype "passive"))
      (node (ref "C24") (pin "1") (pinfunction "1_1") (pintype "passive"))
      (node (ref "C25") (pin "2") (pinfunction "2_2") (pintype "passive"))
      (node (ref "C26") (pin "1") (pinfunction "1_1") (pintype "passive"))
      (node (ref "C27") (pin "2") (pinfunction "2_2") (pintype "passive"))
      (node (ref "C3") (pin "1") (pinfunction "1_1") (pintype "passive"))
      (node (ref "C4") (pin "1") (pinfunction "1_1") (pintype "passive"))
      (node (ref "C5") (pin "1") (pinfunction "1_1") (pintype "passive"))
      (node (ref "C6") (pin "1") (pinfunction "1_1") (pintype "passive"))
      (node (ref "C9") (pin "1") (pinfunction "1_1") (pintype "passive"))
      (node (ref "E1") (pin "2") (pinfunction "2_2") (pintype "passive"))
      (node (ref "HP19") (pin "1") (pinfunction "1_1") (pintype "passive"))
      (node (ref "IC1") (pin "33") (pinfunction "GND_33") (pintype "power_in"))
      (node (ref "IC2") (pin "4") (pinfunction "GND_4") (pintype "power_in"))
      (node (ref "JP1") (pin "1") (pinfunction "1_1") (pintype "passive"))
      (node (ref "JP2") (pin "1") (pinfunction "1_1") (pintype "passive"))
      (node (ref "JP3") (pin "1") (pinfunction "1_1") (pintype "passive"))
      (node (ref "JP4") (pin "6") (pinfunction "6_6") (pintype "passive"))
      (node (ref "L4") (pin "1") (pinfunction "1_1") (pintype "passive"))
      (node (ref "LED1") (pin "2") (pinfunction "K_2") (pintype "passive"))
      (node (ref "LED2") (pin "2") (pinfunction "K_2") (pintype "passive"))
      (node (ref "LED3") (pin "2") (pinfunction "K_2") (pintype "passive"))
      (node (ref "R10") (pin "1") (pinfunction "1_1") (pintype "passive"))
      (node (ref "R11") (pin "2") (pinfunction "2_2") (pintype "passive"))
      (node (ref "R2") (pin "1") (pinfunction "1_1") (pintype "passive"))
      (node (ref "R21") (pin "1") (pinfunction "1_1") (pintype "passive"))
      (node (ref "R22") (pin "2") (pinfunction "2_2") (pintype "passive"))
      (node (ref "R6") (pin "2") (pinfunction "2_2") (pintype "passive"))
      (node (ref "SW1") (pin "3") (pinfunction "3_3") (pintype "passive"))
      (node (ref "SW1") (pin "4") (pinfunction "4_4") (pintype "passive"))
      (node (ref "U1") (pin "10") (pinfunction "PGND3_10") (pintype "passive"))
      (node (ref "U1") (pin "12") (pinfunction "COMPP_12") (pintype "passive"))
      (node (ref "U1") (pin "13") (pinfunction "COMPN_13") (pintype "passive"))
      (node (ref "U1") (pin "14") (pinfunction "GND_14") (pintype "passive"))
      (node (ref "U1") (pin "19") (pinfunction "COMPO#_19") (pintype "passive"))
      (node (ref "U1") (pin "20") (pinfunction "GND_20") (pintype "passive"))
      (node (ref "U1") (pin "21") (pinfunction "NC_21") (pintype "passive"))
      (node (ref "U1") (pin "28") (pinfunction "GND_28") (pintype "passive"))
      (node (ref "U1") (pin "29") (pinfunction "GND_29") (pintype "passive"))
      (node (ref "U1") (pin "6") (pinfunction "PGND1_6") (pintype "passive"))
      (node (ref "U1") (pin "7") (pinfunction "PGND2_7") (pintype "passive"))
      (node (ref "U2") (pin "2") (pinfunction "GND_2") (pintype "passive"))
      (node (ref "U3") (pin "4") (pinfunction "GND_4") (pintype "passive"))
      (node (ref "U3") (pin "8") (pinfunction "DIR_8") (pintype "passive"))
      (node (ref "U4") (pin "2") (pinfunction "GND_2") (pintype "passive"))
      (node (ref "U5") (pin "1") (pinfunction "NC_1") (pintype "passive"))
      (node (ref "U5") (pin "4") (pinfunction "GND_4") (pintype "passive"))
      (node (ref "U5") (pin "7") (pinfunction "REF1_7") (pintype "passive"))
      (node (ref "U6") (pin "1") (pinfunction "NC_1") (pintype "passive"))
      (node (ref "U6") (pin "4") (pinfunction "GND_4") (pintype "passive"))
      (node (ref "U6") (pin "7") (pinfunction "REF1_7") (pintype "passive"))
      (node (ref "U7") (pin "29") (pinfunction "GND_29") (pintype "passive"))
      (node (ref "U7") (pin "3") (pinfunction "GND_3") (pintype "passive"))
      (node (ref "U8") (pin "2") (pinfunction "GND_2") (pintype "passive"))
      (node (ref "USBC1") (pin "0") (pinfunction "0_0") (pintype "passive"))
      (node (ref "USBC1") (pin "A1") (pinfunction "GND_A1") (pintype "passive"))
      (node (ref "USBC1") (pin "A12") (pinfunction "GND_A12") (pintype "passive"))
      (node (ref "USBC1") (pin "B1") (pinfunction "GND_B1") (pintype "passive"))
      (node (ref "USBC1") (pin "B12") (pinfunction "GND_B12") (pintype "passive"))
      (node (ref "USBC2") (pin "0") (pinfunction "0_0") (pintype "passive"))
      (node (ref "USBC2") (pin "A1") (pinfunction "GND_A1") (pintype "passive"))
      (node (ref "USBC2") (pin "A12") (pinfunction "GND_A12") (pintype "passive"))
      (node (ref "USBC2") (pin "B1") (pinfunction "GND_B1") (pintype "passive"))
      (node (ref "USBC2") (pin "B12") (pinfunction "GND_B12") (pintype "passive"))
      (node (ref "X1") (pin "2") (pinfunction "2_2") (pintype "passive"))
      (node (ref "X1") (pin "4") (pinfunction "4_4") (pintype "passive"))
    )
    (net (code "43") (name "Net-(C11-Pad2)") (class "Default")
      (node (ref "C11") (pin "2") (pinfunction "2_2") (pintype "passive"))
      (node (ref "R8") (pin "2") (pinfunction "2_2") (pintype "passive"))
      (node (ref "X1") (pin "1") (pinfunction "1_1") (pintype "passive"))
    )
    (net (code "44") (name "Net-(C17-Pad2)") (class "Default")
      (node (ref "C17") (pin "2") (pinfunction "2_2") (pintype "passive"))
      (node (ref "IC1") (pin "2") (pinfunction "VDD3P3_2") (pintype "power_in"))
      (node (ref "IC1") (pin "3") (pinfunction "VDD3P3_3") (pintype "power_in"))
      (node (ref "L2") (pin "2") (pinfunction "2_2") (pintype "passive"))
    )
    (net (code "45") (name "Net-(C18-Pad2)") (class "Default")
      (node (ref "C18") (pin "2") (pinfunction "2_2") (pintype "passive"))
      (node (ref "C19") (pin "2") (pinfunction "2_2") (pintype "passive"))
      (node (ref "L3") (pin "1") (pinfunction "1_1") (pintype "passive"))
    )
    (net (code "46") (name "Net-(D1-A)") (class "Default")
      (node (ref "D1") (pin "1") (pinfunction "A_1") (pintype "passive"))
      (node (ref "L1") (pin "1") (pinfunction "1_1") (pintype "passive"))
      (node (ref "U2") (pin "1") (pinfunction "SW_1") (pintype "passive"))
    )
    (net (code "47") (name "Net-(IC1-LNA_IN)") (class "Default")
      (node (ref "C19") (pin "1") (pinfunction "1_1") (pintype "passive"))
      (node (ref "IC1") (pin "1") (pinfunction "LNA_IN_1") (pintype "power_in"))
      (node (ref "L4") (pin "2") (pinfunction "2_2") (pintype "passive"))
    )
    (net (code "48") (name "Net-(IC1-P2)") (class "Default")
      (node (ref "IC1") (pin "6") (pinfunction "P2_6") (pintype "power_in"))
      (node (ref "R15") (pin "2") (pinfunction "2_2") (pintype "passive"))
    )
    (net (code "49") (name "Net-(IC1-U0TXD)") (class "Default")
      (node (ref "IC1") (pin "28") (pinfunction "U0TXD_28") (pintype "power_in"))
      (node (ref "R7") (pin "1") (pinfunction "1_1") (pintype "passive"))
    )
    (net (code "50") (name "Net-(IC1-XTAL_N)") (class "Default")
      (node (ref "C12") (pin "1") (pinfunction "1_1") (pintype "passive"))
      (node (ref "IC1") (pin "29") (pinfunction "XTAL_N_29") (pintype "power_in"))
      (node (ref "X1") (pin "3") (pinfunction "3_3") (pintype "passive"))
    )
    (net (code "51") (name "Net-(IC1-XTAL_P)") (class "Default")
      (node (ref "IC1") (pin "30") (pinfunction "XTAL_P_30") (pintype "power_in"))
      (node (ref "R8") (pin "1") (pinfunction "1_1") (pintype "passive"))
    )
    (net (code "52") (name "Net-(LED1-A)") (class "Default")
      (node (ref "LED1") (pin "1") (pinfunction "A_1") (pintype "passive"))
      (node (ref "R3") (pin "1") (pinfunction "1_1") (pintype "passive"))
    )
    (net (code "53") (name "Net-(LED2-A)") (class "Default")
      (node (ref "LED2") (pin "1") (pinfunction "A_1") (pintype "passive"))
      (node (ref "R18") (pin "1") (pinfunction "1_1") (pintype "passive"))
    )
    (net (code "54") (name "Net-(LED3-A)") (class "Default")
      (node (ref "LED3") (pin "1") (pinfunction "A_1") (pintype "passive"))
      (node (ref "R23") (pin "1") (pinfunction "1_1") (pintype "passive"))
    )
    (net (code "55") (name "Net-(LED4-A)") (class "Default")
      (node (ref "LED4") (pin "1") (pinfunction "A_1") (pintype "passive"))
      (node (ref "R25") (pin "2") (pinfunction "2_2") (pintype "passive"))
    )
    (net (code "56") (name "Net-(U1-CP1)") (class "Default")
      (node (ref "C7") (pin "1") (pinfunction "1_1") (pintype "passive"))
      (node (ref "U1") (pin "1") (pinfunction "CP1_1") (pintype "passive"))
    )
    (net (code "57") (name "Net-(U1-CP2)") (class "Default")
      (node (ref "C7") (pin "2") (pinfunction "2_2") (pintype "passive"))
      (node (ref "U1") (pin "2") (pinfunction "CP2_2") (pintype "passive"))
    )
    (net (code "58") (name "Net-(U1-SLEEP#)") (class "Default")
      (node (ref "C6") (pin "2") (pinfunction "2_2") (pintype "passive"))
      (node (ref "U1") (pin "15") (pinfunction "V3P3OUT_15") (pintype "passive"))
      (node (ref "U1") (pin "16") (pinfunction "~{RESET}_16") (pintype "passive"))
      (node (ref "U1") (pin "17") (pinfunction "SLEEP#_17") (pintype "passive"))
    )
    (net (code "59") (name "Net-(U1-VCP)") (class "Default")
      (node (ref "C8") (pin "2") (pinfunction "2_2") (pintype "passive"))
      (node (ref "U1") (pin "3") (pinfunction "VCP_3") (pintype "passive"))
    )
    (net (code "60") (name "Net-(U2-FB)") (class "Default")
      (node (ref "R1") (pin "1") (pinfunction "1_1") (pintype "passive"))
      (node (ref "R2") (pin "2") (pinfunction "2_2") (pintype "passive"))
      (node (ref "U2") (pin "3") (pinfunction "FB_3") (pintype "passive"))
    )
    (net (code "61") (name "Net-(U3-OUT)") (class "Default")
      (node (ref "HP8") (pin "1") (pinfunction "1_1") (pintype "passive"))
      (node (ref "U3") (pin "3") (pinfunction "OUT_3") (pintype "passive"))
    )
    (net (code "62") (name "Net-(U3-PGO)") (class "Default")
      (node (ref "R6") (pin "1") (pinfunction "1_1") (pintype "passive"))
      (node (ref "U3") (pin "5") (pinfunction "PGO_5") (pintype "passive"))
    )
    (net (code "63") (name "Net-(U7-~{RST})") (class "Default")
      (node (ref "R24") (pin "2") (pinfunction "2_2") (pintype "passive"))
      (node (ref "U7") (pin "9") (pinfunction "~{RST}_9") (pintype "passive"))
    )
    (net (code "64") (name "Net-(USBC1-CC1)") (class "Default")
      (node (ref "R11") (pin "1") (pinfunction "1_1") (pintype "passive"))
      (node (ref "USBC1") (pin "A5") (pinfunction "CC1_A5") (pintype "passive"))
    )
    (net (code "65") (name "Net-(USBC1-CC2)") (class "Default")
      (node (ref "R10") (pin "2") (pinfunction "2_2") (pintype "passive"))
      (node (ref "USBC1") (pin "B5") (pinfunction "CC2_B5") (pintype "passive"))
    )
    (net (code "66") (name "Net-(USBC2-CC1)") (class "Default")
      (node (ref "R22") (pin "1") (pinfunction "1_1") (pintype "passive"))
      (node (ref "USBC2") (pin "A5") (pinfunction "CC1_A5") (pintype "passive"))
    )
    (net (code "67") (name "Net-(USBC2-CC2)") (class "Default")
      (node (ref "R21") (pin "2") (pinfunction "2_2") (pintype "passive"))
      (node (ref "USBC2") (pin "B5") (pinfunction "CC2_B5") (pintype "passive"))
    )
    (net (code "68") (name "VCC") (class "Default")
      (node (ref "C1") (pin "2") (pinfunction "2_2") (pintype "passive"))
      (node (ref "C3") (pin "2") (pinfunction "2_2") (pintype "passive"))
      (node (ref "C4") (pin "2") (pinfunction "2_2") (pintype "passive"))
      (node (ref "C5") (pin "2") (pinfunction "2_2") (pintype "passive"))
      (node (ref "C8") (pin "1") (pinfunction "1_1") (pintype "passive"))
      (node (ref "D1") (pin "2") (pinfunction "K_2") (pintype "passive"))
      (node (ref "E1") (pin "1") (pinfunction "1_1") (pintype "passive"))
      (node (ref "R1") (pin "2") (pinfunction "2_2") (pintype "passive"))
      (node (ref "U1") (pin "11") (pinfunction "VM_11") (pintype "passive"))
      (node (ref "U1") (pin "4") (pinfunction "VM_4") (pintype "passive"))
    )
    (net (code "69") (name "unconnected-(L3-Pad2)") (class "Default")
      (node (ref "L3") (pin "2") (pinfunction "2_2") (pintype "passive"))
    )
    (net (code "70") (name "unconnected-(U2-NC-Pad6)") (class "Default")
      (node (ref "U2") (pin "6") (pinfunction "NC_6") (pintype "passive+no_connect"))
    )
    (net (code "71") (name "unconnected-(U4-NC-Pad4)") (class "Default")
      (node (ref "U4") (pin "4") (pinfunction "NC_4") (pintype "passive+no_connect"))
    )
    (net (code "72") (name "unconnected-(U7-CTS-Pad23)") (class "Default")
      (node (ref "U7") (pin "23") (pinfunction "CTS_23") (pintype "passive+no_connect"))
    )
    (net (code "73") (name "unconnected-(U7-DCD-Pad1)") (class "Default")
      (node (ref "U7") (pin "1") (pinfunction "DCD_1") (pintype "passive+no_connect"))
    )
    (net (code "74") (name "unconnected-(U7-DSR-Pad27)") (class "Default")
      (node (ref "U7") (pin "27") (pinfunction "DSR_27") (pintype "passive+no_connect"))
    )
    (net (code "75") (name "unconnected-(U7-NC-Pad10)") (class "Default")
      (node (ref "U7") (pin "10") (pinfunction "NC_10") (pintype "passive+no_connect"))
    )
    (net (code "76") (name "unconnected-(U7-NC-Pad13)") (class "Default")
      (node (ref "U7") (pin "13") (pinfunction "NC_13") (pintype "passive+no_connect"))
    )
    (net (code "77") (name "unconnected-(U7-NC-Pad14)") (class "Default")
      (node (ref "U7") (pin "14") (pinfunction "NC_14") (pintype "passive+no_connect"))
    )
    (net (code "78") (name "unconnected-(U7-NC-Pad15)") (class "Default")
      (node (ref "U7") (pin "15") (pinfunction "NC_15") (pintype "passive+no_connect"))
    )
    (net (code "79") (name "unconnected-(U7-NC-Pad16)") (class "Default")
      (node (ref "U7") (pin "16") (pinfunction "NC_16") (pintype "passive+no_connect"))
    )
    (net (code "80") (name "unconnected-(U7-NC-Pad17)") (class "Default")
      (node (ref "U7") (pin "17") (pinfunction "NC_17") (pintype "passive+no_connect"))
    )
    (net (code "81") (name "unconnected-(U7-NC-Pad19)") (class "Default")
      (node (ref "U7") (pin "19") (pinfunction "NC_19") (pintype "passive+no_connect"))
    )
    (net (code "82") (name "unconnected-(U7-NC-Pad20)") (class "Default")
      (node (ref "U7") (pin "20") (pinfunction "NC_20") (pintype "passive+no_connect"))
    )
    (net (code "83") (name "unconnected-(U7-NC-Pad21)") (class "Default")
      (node (ref "U7") (pin "21") (pinfunction "NC_21") (pintype "passive+no_connect"))
    )
    (net (code "84") (name "unconnected-(U7-NC-Pad22)") (class "Default")
      (node (ref "U7") (pin "22") (pinfunction "NC_22") (pintype "passive+no_connect"))
    )
    (net (code "85") (name "unconnected-(U7-NC{slash}VPP-Pad18)") (class "Default")
      (node (ref "U7") (pin "18") (pinfunction "NC/VPP_18") (pintype "passive+no_connect"))
    )
    (net (code "86") (name "unconnected-(U7-RI-Pad2)") (class "Default")
      (node (ref "U7") (pin "2") (pinfunction "RI_2") (pintype "passive+no_connect"))
    )
    (net (code "87") (name "unconnected-(U7-SUSPEND-Pad12)") (class "Default")
      (node (ref "U7") (pin "12") (pinfunction "SUSPEND_12") (pintype "passive+no_connect"))
    )
    (net (code "88") (name "unconnected-(U7-~{SUSPEND}-Pad11)") (class "Default")
      (node (ref "U7") (pin "11") (pinfunction "~{SUSPEND}_11") (pintype "passive+no_connect"))
    )
    (net (code "89") (name "unconnected-(U8-NC-Pad4)") (class "Default")
      (node (ref "U8") (pin "4") (pinfunction "NC_4") (pintype "passive+no_connect"))
    )
    (net (code "90") (name "unconnected-(USBC1-SBU1-PadA8)") (class "Default")
      (node (ref "USBC1") (pin "A8") (pinfunction "SBU1_A8") (pintype "passive+no_connect"))
    )
    (net (code "91") (name "unconnected-(USBC1-SBU2-PadB8)") (class "Default")
      (node (ref "USBC1") (pin "B8") (pinfunction "SBU2_B8") (pintype "passive+no_connect"))
    )
    (net (code "92") (name "unconnected-(USBC2-SBU1-PadA8)") (class "Default")
      (node (ref "USBC2") (pin "A8") (pinfunction "SBU1_A8") (pintype "passive+no_connect"))
    )
    (net (code "93") (name "unconnected-(USBC2-SBU2-PadB8)") (class "Default")
      (node (ref "USBC2") (pin "B8") (pinfunction "SBU2_B8") (pintype "passive+no_connect"))
    )
  )
)
